# Headers.net
KiCad netlist of a schematic drawn in Altium Designer
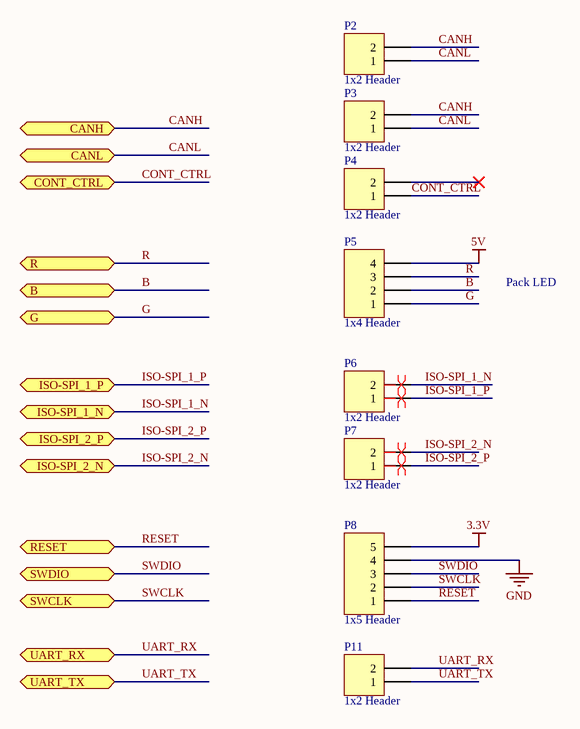
[diagram p0: Headers.SchDoc]

(export (version "E")
  (design (tool "Eeschema 10.0.6"))
  (components
    (comp (ref "P2")
      (value "1x2 Header")
      (footprint "HDR1X2")
      (description "1x2 Pin Header")
      (libsource (lib "GeneralConnectors") (part "1x2 Header"))
    )
    (comp (ref "P3")
      (value "1x2 Header")
      (footprint "HDR1X2")
      (description "1x2 Pin Header")
      (libsource (lib "GeneralConnectors") (part "1x2 Header"))
    )
    (comp (ref "P4")
      (value "1x2 Header")
      (footprint "HDR1X2")
      (description "1x2 Pin Header")
      (libsource (lib "GeneralConnectors") (part "1x2 Header"))
    )
    (comp (ref "P5")
      (value "1x4 Header")
      (footprint "HDR1X4")
      (description "1x4 Pin Header")
      (libsource (lib "GeneralConnectors") (part "1x4 Header"))
    )
    (comp (ref "P6")
      (value "1x2 Header")
      (footprint "HDR1X2")
      (description "1x2 Pin Header")
      (libsource (lib "GeneralConnectors") (part "1x2 Header"))
    )
    (comp (ref "P7")
      (value "1x2 Header")
      (footprint "HDR1X2")
      (description "1x2 Pin Header")
      (libsource (lib "GeneralConnectors") (part "1x2 Header"))
    )
    (comp (ref "P8")
      (value "1x5 Header")
      (footprint "HDR1X5")
      (description "1x5 Pin Header")
      (libsource (lib "GeneralConnectors") (part "1x5 Header"))
    )
    (comp (ref "P11")
      (value "1x2 Header")
      (footprint "HDR1X2")
      (description "1x2 Pin Header")
      (libsource (lib "GeneralConnectors") (part "1x2 Header"))
    )
  )
  (nets
    (net (code "1") (name "/B") (class "Default")
      (node (ref "P5") (pin "2") (pinfunction "2_2") (pintype "passive"))
    )
    (net (code "2") (name "/CANH") (class "Default")
      (node (ref "P2") (pin "2") (pinfunction "2_2") (pintype "passive"))
      (node (ref "P3") (pin "2") (pinfunction "2_2") (pintype "passive"))
    )
    (net (code "3") (name "/CANL") (class "Default")
      (node (ref "P2") (pin "1") (pinfunction "1_1") (pintype "passive"))
      (node (ref "P3") (pin "1") (pinfunction "1_1") (pintype "passive"))
    )
    (net (code "4") (name "/CONT_CTRL") (class "Default")
      (node (ref "P4") (pin "1") (pinfunction "1_1") (pintype "passive"))
    )
    (net (code "5") (name "/G") (class "Default")
      (node (ref "P5") (pin "1") (pinfunction "1_1") (pintype "passive"))
    )
    (net (code "6") (name "/ISO-SPI_1_N") (class "Default")
      (node (ref "P6") (pin "2") (pinfunction "2_2") (pintype "passive"))
    )
    (net (code "7") (name "/ISO-SPI_1_P") (class "Default")
      (node (ref "P6") (pin "1") (pinfunction "1_1") (pintype "passive"))
    )
    (net (code "8") (name "/ISO-SPI_2_N") (class "Default")
      (node (ref "P7") (pin "2") (pinfunction "2_2") (pintype "passive"))
    )
    (net (code "9") (name "/ISO-SPI_2_P") (class "Default")
      (node (ref "P7") (pin "1") (pinfunction "1_1") (pintype "passive"))
    )
    (net (code "10") (name "/R") (class "Default")
      (node (ref "P5") (pin "3") (pinfunction "3_3") (pintype "passive"))
    )
    (net (code "11") (name "/RESET") (class "Default")
      (node (ref "P8") (pin "1") (pinfunction "1_1") (pintype "passive"))
    )
    (net (code "12") (name "/SWCLK") (class "Default")
      (node (ref "P8") (pin "2") (pinfunction "2_2") (pintype "passive"))
    )
    (net (code "13") (name "/SWDIO") (class "Default")
      (node (ref "P8") (pin "3") (pinfunction "3_3") (pintype "passive"))
    )
    (net (code "14") (name "/UART_RX") (class "Default")
      (node (ref "P11") (pin "2") (pinfunction "2_2") (pintype "passive"))
    )
    (net (code "15") (name "/UART_TX") (class "Default")
      (node (ref "P11") (pin "1") (pinfunction "1_1") (pintype "passive"))
    )
    (net (code "16") (name "3.3V") (class "Default")
      (node (ref "P8") (pin "5") (pinfunction "5_5") (pintype "passive"))
    )
    (net (code "17") (name "5V") (class "Default")
      (node (ref "P5") (pin "4") (pinfunction "4_4") (pintype "passive"))
    )
    (net (code "18") (name "GND") (class "Default")
      (node (ref "P8") (pin "4") (pinfunction "4_4") (pintype "passive"))
    )
    (net (code "19") (name "unconnected-(P4-Pad2)") (class "Default")
      (node (ref "P4") (pin "2") (pinfunction "2_2") (pintype "passive+no_connect"))
    )
  )
)
